# TPS6120x.net
KiCad netlist of a schematic drawn in Altium Designer
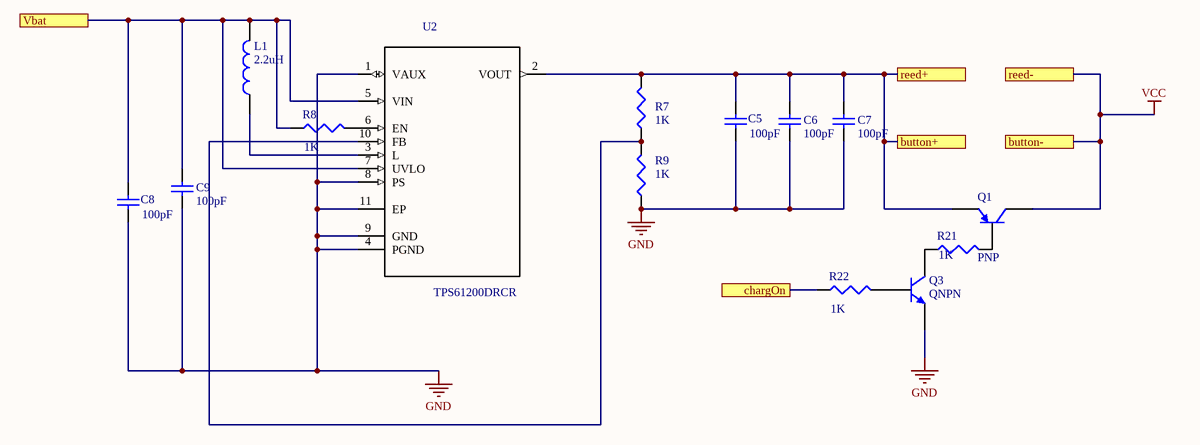
[diagram p0: TPS6120x.SchDoc]

(export (version "E")
  (design (tool "Eeschema 10.0.6"))
  (components
    (comp (ref "C5")
      (value "100pF")
      (footprint "C1206")
      (description "Capacitor (Semiconductor SIM Model)")
      (fields (field (name "Comment") "Cap Semi") (field (name "PUBLISHER") "Altium Limited"))
      (libsource (lib "Miscellaneous Devices") (part "Cap Semi"))
    )
    (comp (ref "C6")
      (value "100pF")
      (footprint "C1206")
      (description "Capacitor (Semiconductor SIM Model)")
      (fields (field (name "Comment") "Cap Semi") (field (name "PUBLISHER") "Altium Limited"))
      (libsource (lib "Miscellaneous Devices") (part "Cap Semi"))
    )
    (comp (ref "C7")
      (value "100pF")
      (footprint "C1206")
      (description "Capacitor (Semiconductor SIM Model)")
      (fields (field (name "Comment") "Cap Semi") (field (name "PUBLISHER") "Altium Limited"))
      (libsource (lib "Miscellaneous Devices") (part "Cap Semi"))
    )
    (comp (ref "C8")
      (value "100pF")
      (footprint "C1206")
      (description "Capacitor (Semiconductor SIM Model)")
      (fields (field (name "Comment") "Cap Semi") (field (name "PUBLISHER") "Altium Limited"))
      (libsource (lib "Miscellaneous Devices") (part "Cap Semi"))
    )
    (comp (ref "C9")
      (value "100pF")
      (footprint "C1206")
      (description "Capacitor (Semiconductor SIM Model)")
      (fields (field (name "Comment") "Cap Semi") (field (name "PUBLISHER") "Altium Limited"))
      (libsource (lib "Miscellaneous Devices") (part "Cap Semi"))
    )
    (comp (ref "L1")
      (value "2.2uH")
      (footprint "WE-TPC_2828")
      (description "WE-TPC SMD Shielded Tiny Power Inductor, size 2828, 1.8A, 57mΩ, 2.2uH")
      (fields (field (name "PART NUMBER") "744025002") (field (name "PUBLISHER") "Wurth Elektronik"))
      (libsource (lib "ALTIUM-WE-TPC-rev17a") (part "744025002"))
    )
    (comp (ref "Q1")
      (value "PNP")
      (footprint "SOT-23B_N")
      (description "PNP Bipolar Transistor")
      (fields (field (name "PUBLISHER") "Altium Limited"))
      (libsource (lib "Miscellaneous Devices") (part "PNP"))
    )
    (comp (ref "Q3")
      (value "QNPN")
      (footprint "SOT-23B_N")
      (description "NPN Bipolar Transistor")
      (fields (field (name "PUBLISHER") "Altium Limited"))
      (libsource (lib "Miscellaneous Devices") (part "QNPN"))
    )
    (comp (ref "R7")
      (value "1K")
      (footprint "J1-0603")
      (description "Resistor")
      (fields (field (name "Comment") "Res3") (field (name "PUBLISHER") "Altium Limited"))
      (libsource (lib "Miscellaneous Devices") (part "Res3"))
    )
    (comp (ref "R8")
      (value "1K")
      (footprint "J1-0603")
      (description "Resistor")
      (fields (field (name "Comment") "Res3") (field (name "PUBLISHER") "Altium Limited"))
      (libsource (lib "Miscellaneous Devices") (part "Res3"))
    )
    (comp (ref "R9")
      (value "1K")
      (footprint "J1-0603")
      (description "Resistor")
      (fields (field (name "Comment") "Res3") (field (name "PUBLISHER") "Altium Limited"))
      (libsource (lib "Miscellaneous Devices") (part "Res3"))
    )
    (comp (ref "R21")
      (value "1K")
      (footprint "J1-0603")
      (description "Resistor")
      (fields (field (name "Comment") "Res3") (field (name "PUBLISHER") "Altium Limited"))
      (libsource (lib "Miscellaneous Devices") (part "Res3"))
    )
    (comp (ref "R22")
      (value "1K")
      (footprint "J1-0603")
      (description "Resistor")
      (fields (field (name "Comment") "Res3") (field (name "PUBLISHER") "Altium Limited"))
      (libsource (lib "Miscellaneous Devices") (part "Res3"))
    )
    (comp (ref "U2")
      (value "TPS61200DRCR")
      (footprint "SON50P300X300X100-11N")
      (description "0.3V Input Voltage Boost Converter with 1.3A Switches and 'Down Mode' in 3x3 QFN 10-VSON -40 to 85")
      (fields (field (name "MF") "Texas Instruments"))
      (libsource (lib "HGCDLibrary") (part "TPS61200DRCR"))
    )
  )
  (nets
    (net (code "1") (name "/Vbat") (class "Default")
      (node (ref "C8") (pin "1") (pinfunction "1_1") (pintype "passive"))
      (node (ref "C9") (pin "2") (pinfunction "2_2") (pintype "passive"))
      (node (ref "L1") (pin "2") (pinfunction "2_2") (pintype "passive"))
      (node (ref "R8") (pin "1") (pinfunction "1_1") (pintype "passive"))
      (node (ref "U2") (pin "5") (pinfunction "VIN_5") (pintype "input"))
      (node (ref "U2") (pin "7") (pinfunction "UVLO_7") (pintype "input"))
    )
    (net (code "2") (name "/button+") (class "Default")
      (node (ref "C5") (pin "1") (pinfunction "1_1") (pintype "passive"))
      (node (ref "C6") (pin "2") (pinfunction "2_2") (pintype "passive"))
      (node (ref "C7") (pin "2") (pinfunction "2_2") (pintype "passive"))
      (node (ref "Q1") (pin "3") (pinfunction "E_3") (pintype "passive"))
      (node (ref "R7") (pin "2") (pinfunction "2_2") (pintype "passive"))
      (node (ref "U2") (pin "2") (pinfunction "VOUT_2") (pintype "output"))
    )
    (net (code "3") (name "/chargOn") (class "Default")
      (node (ref "R22") (pin "1") (pinfunction "1_1") (pintype "passive"))
    )
    (net (code "4") (name "GND") (class "Default")
      (node (ref "C5") (pin "2") (pinfunction "2_2") (pintype "passive"))
      (node (ref "C6") (pin "1") (pinfunction "1_1") (pintype "passive"))
      (node (ref "C7") (pin "1") (pinfunction "1_1") (pintype "passive"))
      (node (ref "C8") (pin "2") (pinfunction "2_2") (pintype "passive"))
      (node (ref "C9") (pin "1") (pinfunction "1_1") (pintype "passive"))
      (node (ref "Q3") (pin "3") (pinfunction "E_3") (pintype "passive"))
      (node (ref "R9") (pin "1") (pinfunction "1_1") (pintype "passive"))
      (node (ref "U2") (pin "1") (pinfunction "VAUX_1") (pintype "bidirectional"))
      (node (ref "U2") (pin "11") (pinfunction "EP_11") (pintype "passive"))
      (node (ref "U2") (pin "4") (pinfunction "PGND_4") (pintype "passive"))
      (node (ref "U2") (pin "8") (pinfunction "PS_8") (pintype "input"))
      (node (ref "U2") (pin "9") (pinfunction "GND_9") (pintype "passive"))
    )
    (net (code "5") (name "Net-(Q1-B)") (class "Default")
      (node (ref "Q1") (pin "2") (pinfunction "B_2") (pintype "passive"))
      (node (ref "R21") (pin "2") (pinfunction "2_2") (pintype "passive"))
    )
    (net (code "6") (name "Net-(Q3-B)") (class "Default")
      (node (ref "Q3") (pin "2") (pinfunction "B_2") (pintype "passive"))
      (node (ref "R22") (pin "2") (pinfunction "2_2") (pintype "passive"))
    )
    (net (code "7") (name "Net-(Q3-C)") (class "Default")
      (node (ref "Q3") (pin "1") (pinfunction "C_1") (pintype "passive"))
      (node (ref "R21") (pin "1") (pinfunction "1_1") (pintype "passive"))
    )
    (net (code "8") (name "Net-(U2-EN)") (class "Default")
      (node (ref "R8") (pin "2") (pinfunction "2_2") (pintype "passive"))
      (node (ref "U2") (pin "6") (pinfunction "EN_6") (pintype "input"))
    )
    (net (code "9") (name "Net-(U2-FB)") (class "Default")
      (node (ref "R7") (pin "1") (pinfunction "1_1") (pintype "passive"))
      (node (ref "R9") (pin "2") (pinfunction "2_2") (pintype "passive"))
      (node (ref "U2") (pin "10") (pinfunction "FB_10") (pintype "input"))
    )
    (net (code "10") (name "Net-(U2-L)") (class "Default")
      (node (ref "L1") (pin "1") (pinfunction "1_1") (pintype "passive"))
      (node (ref "U2") (pin "3") (pinfunction "L_3") (pintype "input"))
    )
    (net (code "11") (name "VCC") (class "Default")
      (node (ref "Q1") (pin "1") (pinfunction "C_1") (pintype "passive"))
    )
  )
)
